# TwistIt.net
KiCad netlist of a schematic drawn in EAGLE
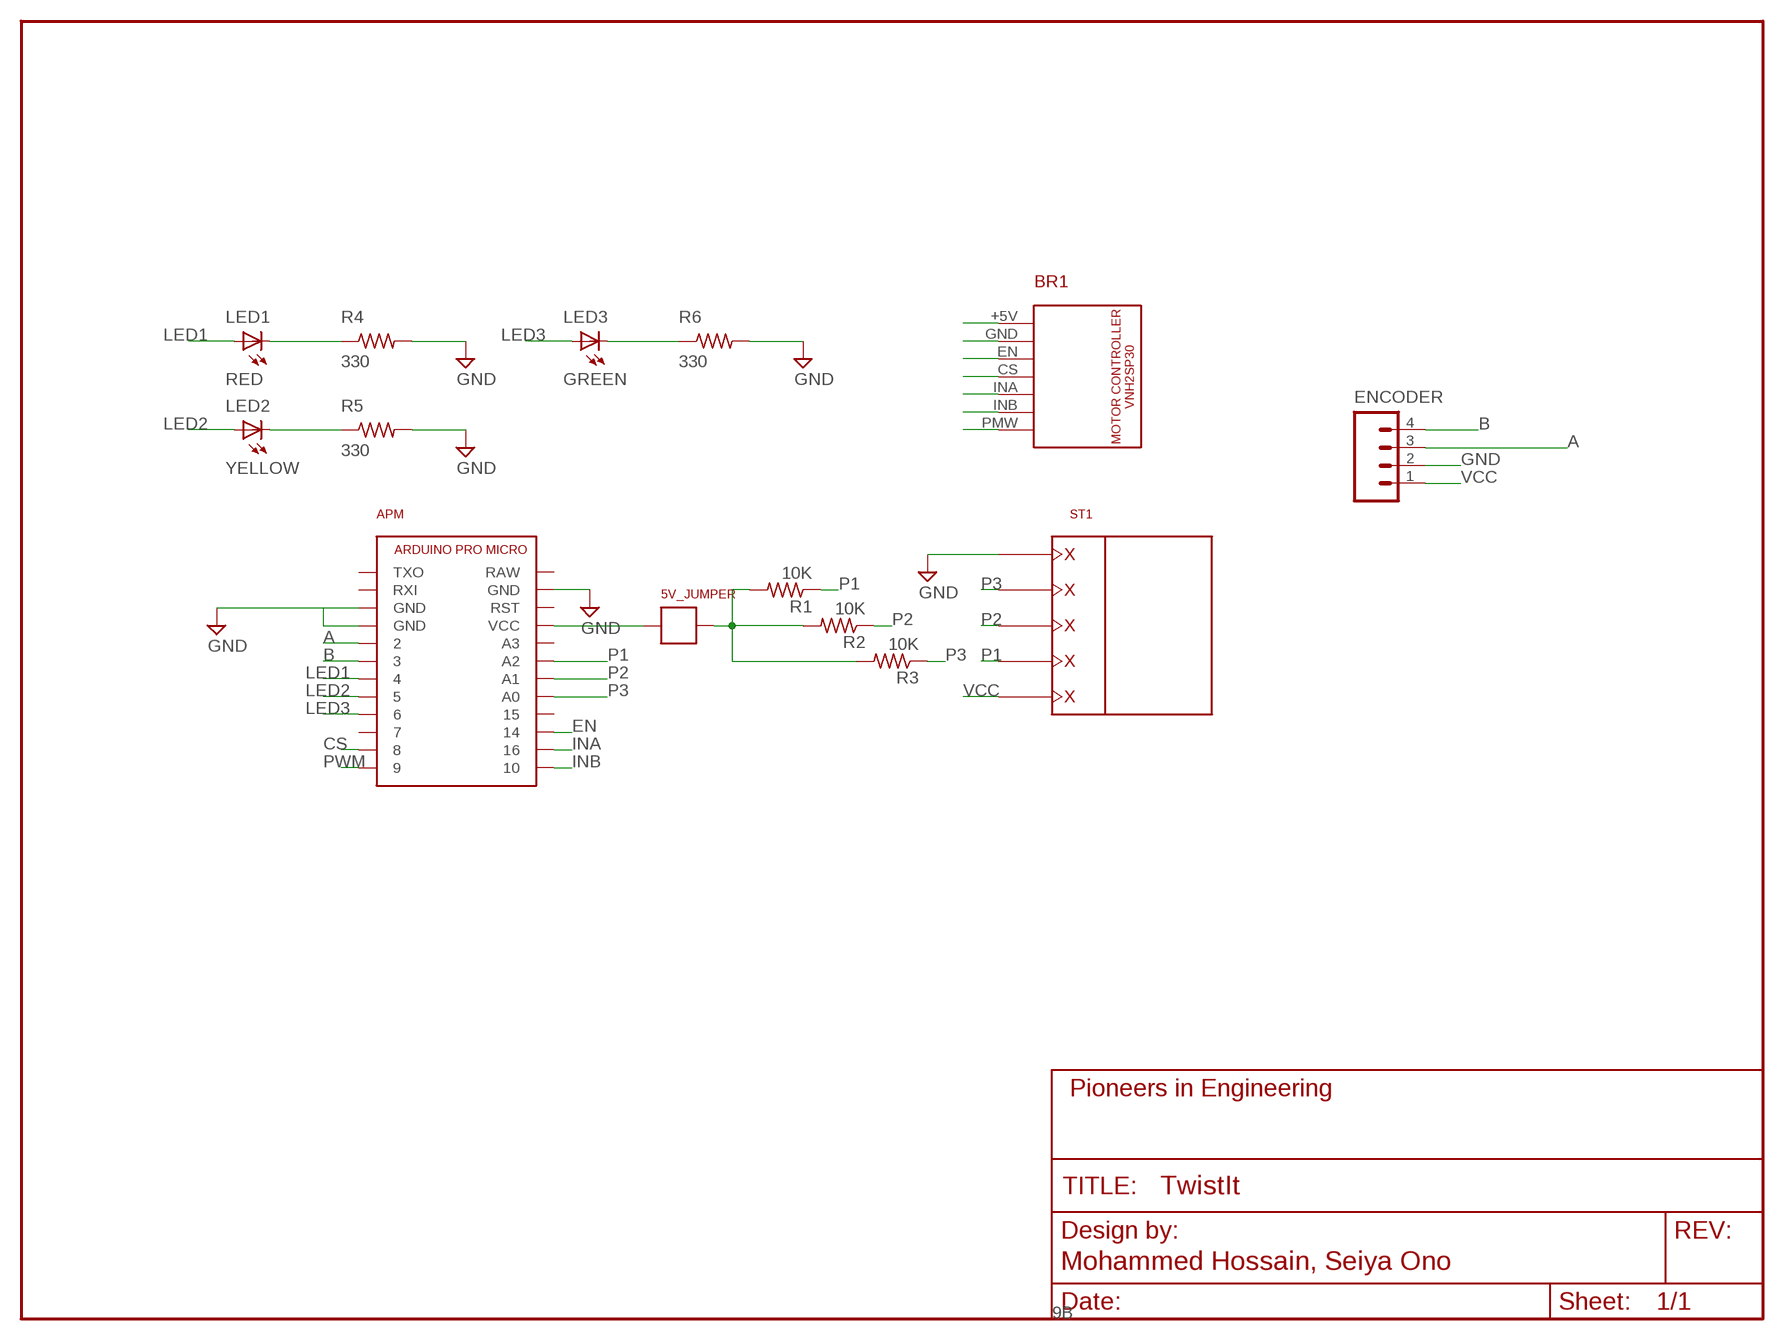
[diagram p0: schematic, sheet 1]

(export (version "E")
  (design (tool "Eeschema 10.0.6"))
  (components
    (comp (ref "5V_JUMPER")
      (value "JUMPER")
      (footprint "eagle-import:JUMPER")
      (fields
        (field (name "DISTRIBUTOR_PART_NUMBER") "952-2262-ND")
        (field (name "MANUFACTURER") "Harwin. Inc")
        (field (name "MANUFACTURER_PART_NUMBER") "M20-9990246")
      )
      (libsource (lib "eagle-import") (part "JUMPER"))
    )
    (comp (ref "APM")
      (value "ARDUINO_PRO_MICRO")
      (footprint "eagle-import:ARDUINO_PRO_MICRO")
      (fields
        (field (name "DISTRIBUTOR_PART_NUMBER") "32284746884")
        (field (name "MANUFACTURER") "Feiyang electronics")
      )
      (libsource (lib "eagle-import") (part "ARDUINO_PRO_MICRO"))
    )
    (comp (ref "BR1")
      (value "VNH2SP30_MOTOR_CONTROLLER")
      (footprint "eagle-import:VNH2SP30_MOTOR_CONTROLLER")
      (libsource (lib "eagle-import") (part "VNH2SP30_MOTOR_CONTROLLER"))
    )
    (comp (ref "ENCODER")
      (value "M041X04-MTA")
      (footprint "eagle-import:1X04-MTA")
      (libsource (lib "eagle-import") (part "M041X04-MTA"))
    )
    (comp (ref "LED1")
      (value "RED")
      (footprint "eagle-import:FKIT-LED-1206")
      (libsource (lib "eagle-import") (part "LED-FKIT-1206"))
    )
    (comp (ref "LED2")
      (value "YELLOW")
      (footprint "eagle-import:FKIT-LED-1206")
      (libsource (lib "eagle-import") (part "LED-FKIT-1206"))
    )
    (comp (ref "LED3")
      (value "GREEN")
      (footprint "eagle-import:FKIT-LED-1206")
      (libsource (lib "eagle-import") (part "LED-FKIT-1206"))
    )
    (comp (ref "R1")
      (value "10K")
      (footprint "eagle-import:R0603")
      (libsource (lib "eagle-import") (part "resistor_R-US_R0603"))
    )
    (comp (ref "R2")
      (value "10K")
      (footprint "eagle-import:R0603")
      (libsource (lib "eagle-import") (part "resistor_R-US_R0603"))
    )
    (comp (ref "R3")
      (value "10K")
      (footprint "eagle-import:R0603")
      (libsource (lib "eagle-import") (part "resistor_R-US_R0603"))
    )
    (comp (ref "R4")
      (value "330")
      (footprint "eagle-import:R0603")
      (fields (field (name "MANUFACTURER") "Rohm Semiconductor"))
      (libsource (lib "eagle-import") (part "R-US_R0603"))
    )
    (comp (ref "R5")
      (value "330")
      (footprint "eagle-import:R0603")
      (fields (field (name "MANUFACTURER") "Rohm Semiconductor"))
      (libsource (lib "eagle-import") (part "R-US_R0603"))
    )
    (comp (ref "R6")
      (value "330")
      (footprint "eagle-import:R0603")
      (fields (field (name "MANUFACTURER") "Rohm Semiconductor"))
      (libsource (lib "eagle-import") (part "R-US_R0603"))
    )
    (comp (ref "ST1")
      (value "5PIN_SCREW")
      (footprint "eagle-import:5PIN_SCREW")
      (fields
        (field (name "DISTRIBUTOR_PART_NUMBER") "277-1239-ND")
        (field (name "MANUFACTURER") "Phoenix Contact")
        (field (name "MANUFACTURER_PART_NUMBER") "1729047")
      )
      (libsource (lib "eagle-import") (part "5PIN_SCREW"))
    )
  )
  (nets
    (net (code "1") (name "/A") (class "Default")
      (node (ref "APM") (pin "2") (pinfunction "2_2") (pintype "bidirectional"))
      (node (ref "ENCODER") (pin "3") (pinfunction "3_3") (pintype "passive"))
    )
    (net (code "2") (name "/B") (class "Default")
      (node (ref "APM") (pin "3") (pinfunction "3_3") (pintype "bidirectional"))
      (node (ref "ENCODER") (pin "4") (pinfunction "4_4") (pintype "passive"))
    )
    (net (code "3") (name "/CS") (class "Default")
      (node (ref "APM") (pin "8") (pinfunction "8_8") (pintype "bidirectional"))
      (node (ref "BR1") (pin "CS") (pinfunction "CS_CS") (pintype "bidirectional"))
    )
    (net (code "4") (name "/EN") (class "Default")
      (node (ref "APM") (pin "14") (pinfunction "14_14") (pintype "bidirectional"))
      (node (ref "BR1") (pin "EN") (pinfunction "EN_EN") (pintype "bidirectional"))
    )
    (net (code "5") (name "/INA") (class "Default")
      (node (ref "APM") (pin "16") (pinfunction "16_16") (pintype "bidirectional"))
      (node (ref "BR1") (pin "INA") (pinfunction "INA_INA") (pintype "bidirectional"))
    )
    (net (code "6") (name "/INB") (class "Default")
      (node (ref "APM") (pin "10") (pinfunction "10_10") (pintype "bidirectional"))
      (node (ref "BR1") (pin "INB") (pinfunction "INB_INB") (pintype "bidirectional"))
    )
    (net (code "7") (name "/LED1") (class "Default")
      (node (ref "APM") (pin "4") (pinfunction "4_4") (pintype "bidirectional"))
      (node (ref "LED1") (pin "A") (pinfunction "A_A") (pintype "passive"))
    )
    (net (code "8") (name "/LED2") (class "Default")
      (node (ref "APM") (pin "5") (pinfunction "5_5") (pintype "bidirectional"))
      (node (ref "LED2") (pin "A") (pinfunction "A_A") (pintype "passive"))
    )
    (net (code "9") (name "/LED3") (class "Default")
      (node (ref "APM") (pin "6") (pinfunction "6_6") (pintype "bidirectional"))
      (node (ref "LED3") (pin "A") (pinfunction "A_A") (pintype "passive"))
    )
    (net (code "10") (name "/P1") (class "Default")
      (node (ref "APM") (pin "A2") (pinfunction "A2_A2") (pintype "bidirectional"))
      (node (ref "R1") (pin "1") (pinfunction "1_1") (pintype "passive"))
      (node (ref "ST1") (pin "P$4") (pinfunction "P$4_P$4") (pintype "bidirectional"))
    )
    (net (code "11") (name "/P2") (class "Default")
      (node (ref "APM") (pin "A1") (pinfunction "A1_A1") (pintype "bidirectional"))
      (node (ref "R2") (pin "1") (pinfunction "1_1") (pintype "passive"))
      (node (ref "ST1") (pin "P$3") (pinfunction "P$3_P$3") (pintype "bidirectional"))
    )
    (net (code "12") (name "/P3") (class "Default")
      (node (ref "APM") (pin "A0") (pinfunction "A0_A0") (pintype "bidirectional"))
      (node (ref "R3") (pin "1") (pinfunction "1_1") (pintype "passive"))
      (node (ref "ST1") (pin "P$2") (pinfunction "P$2_P$2") (pintype "bidirectional"))
    )
    (net (code "13") (name "/PWM") (class "Default")
      (node (ref "APM") (pin "9") (pinfunction "9_9") (pintype "bidirectional"))
      (node (ref "BR1") (pin "PMW") (pinfunction "PMW_PMW") (pintype "bidirectional"))
    )
    (net (code "14") (name "/VCC") (class "Default")
      (node (ref "5V_JUMPER") (pin "P$1") (pinfunction "P$1_P$1") (pintype "input"))
      (node (ref "APM") (pin "VCC") (pinfunction "VCC_VCC") (pintype "bidirectional"))
      (node (ref "BR1") (pin "+5V") (pinfunction "+5V_+5V") (pintype "bidirectional"))
      (node (ref "ENCODER") (pin "1") (pinfunction "1_1") (pintype "passive"))
      (node (ref "ST1") (pin "P$5") (pinfunction "P$5_P$5") (pintype "bidirectional"))
    )
    (net (code "15") (name "GND") (class "Default")
      (node (ref "APM") (pin "GND@0") (pinfunction "GND_GND@0") (pintype "bidirectional"))
      (node (ref "APM") (pin "GND@1") (pinfunction "GND_GND@1") (pintype "bidirectional"))
      (node (ref "APM") (pin "GND@2") (pinfunction "GND_GND@2") (pintype "bidirectional"))
      (node (ref "BR1") (pin "GND") (pinfunction "GND_GND") (pintype "bidirectional"))
      (node (ref "ENCODER") (pin "2") (pinfunction "2_2") (pintype "passive"))
      (node (ref "R4") (pin "2") (pinfunction "2_2") (pintype "passive"))
      (node (ref "R5") (pin "2") (pinfunction "2_2") (pintype "passive"))
      (node (ref "R6") (pin "2") (pinfunction "2_2") (pintype "passive"))
      (node (ref "ST1") (pin "P$1") (pinfunction "P$1_P$1") (pintype "bidirectional"))
    )
    (net (code "16") (name "Net-(5V_JUMPER-PadP$2)") (class "Default")
      (node (ref "5V_JUMPER") (pin "P$2") (pinfunction "P$2_P$2") (pintype "bidirectional"))
      (node (ref "R1") (pin "2") (pinfunction "2_2") (pintype "passive"))
      (node (ref "R2") (pin "2") (pinfunction "2_2") (pintype "passive"))
      (node (ref "R3") (pin "2") (pinfunction "2_2") (pintype "passive"))
    )
    (net (code "17") (name "Net-(LED1-PadC)") (class "Default")
      (node (ref "LED1") (pin "C") (pinfunction "C_C") (pintype "passive"))
      (node (ref "R4") (pin "1") (pinfunction "1_1") (pintype "passive"))
    )
    (net (code "18") (name "Net-(LED2-PadC)") (class "Default")
      (node (ref "LED2") (pin "C") (pinfunction "C_C") (pintype "passive"))
      (node (ref "R5") (pin "1") (pinfunction "1_1") (pintype "passive"))
    )
    (net (code "19") (name "Net-(LED3-PadC)") (class "Default")
      (node (ref "LED3") (pin "C") (pinfunction "C_C") (pintype "passive"))
      (node (ref "R6") (pin "1") (pinfunction "1_1") (pintype "passive"))
    )
    (net (code "20") (name "unconnected-(APM-Pad7)") (class "Default")
      (node (ref "APM") (pin "7") (pinfunction "7_7") (pintype "bidirectional"))
    )
    (net (code "21") (name "unconnected-(APM-Pad15)") (class "Default")
      (node (ref "APM") (pin "15") (pinfunction "15_15") (pintype "bidirectional"))
    )
    (net (code "22") (name "unconnected-(APM-PadA3)") (class "Default")
      (node (ref "APM") (pin "A3") (pinfunction "A3_A3") (pintype "bidirectional"))
    )
    (net (code "23") (name "unconnected-(APM-PadRAW)") (class "Default")
      (node (ref "APM") (pin "RAW") (pinfunction "RAW_RAW") (pintype "bidirectional"))
    )
    (net (code "24") (name "unconnected-(APM-PadRST)") (class "Default")
      (node (ref "APM") (pin "RST") (pinfunction "RST_RST") (pintype "bidirectional"))
    )
    (net (code "25") (name "unconnected-(APM-PadRXI)") (class "Default")
      (node (ref "APM") (pin "RXI") (pinfunction "RXI_RXI") (pintype "bidirectional"))
    )
    (net (code "26") (name "unconnected-(APM-PadTXO)") (class "Default")
      (node (ref "APM") (pin "TXO") (pinfunction "TXO_TXO") (pintype "bidirectional"))
    )
  )
)
